# Xbee.net
KiCad netlist of a schematic drawn in Altium Designer
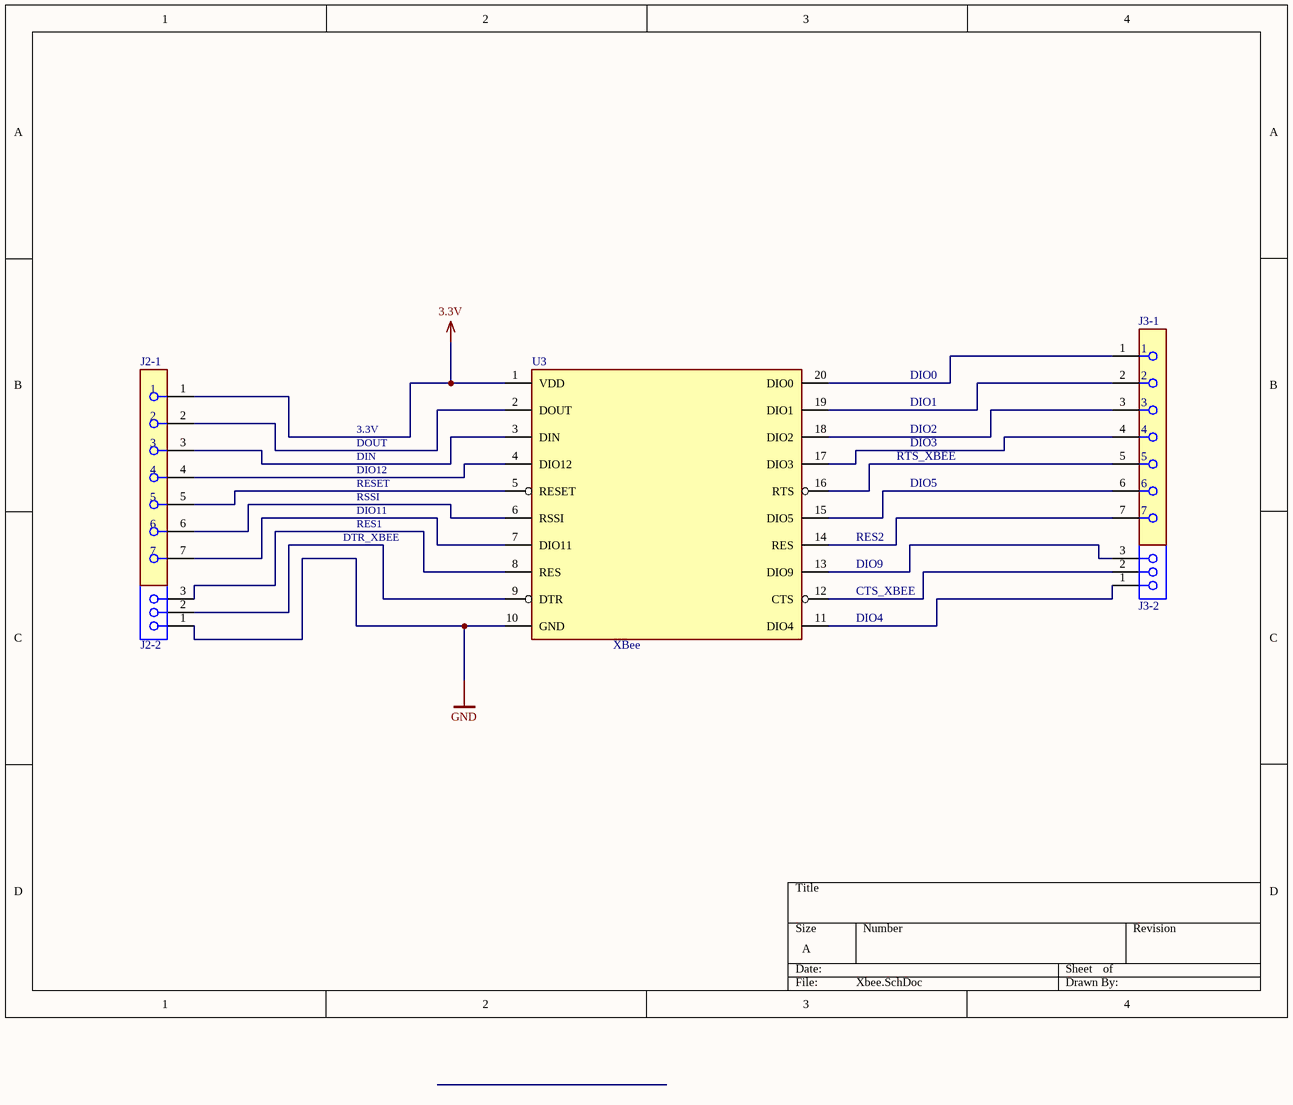
[diagram p0: Xbee.SchDoc]

(export (version "E")
  (design (tool "Eeschema 10.0.6"))
  (components
    (comp (ref "J2-1")
      (value "SSM-107-L-SV-BE")
      (footprint "FP-SSM-107-L-SV-BE-MFG")
      (description "CONN RCPT 7POS 0.1 GOLD SMD")
      (libsource (lib "") (part "e5664c6fdf629e95b354a88b8d4375b_1"))
    )
    (comp (ref "J2-2")
      (value "SSM-103-L-SV")
      (footprint "SMTC-SSM-103-X-SV")
      (description "Tiger Claw(TM) Surface Mount Socket, Vertical, -55 to 125 degC, 2.54 mm Pitch, 3-Pin, Female, RoHS")
      (fields (field (name "MANUFACTURER") "Samtec"))
      (libsource (lib "Altium Content Vault") (part "SMTC-SSM-103-X-SV"))
    )
    (comp (ref "J3-1")
      (value "SSM-107-L-SV-BE")
      (footprint "FP-SSM-107-L-SV-BE-MFG")
      (description "CONN RCPT 7POS 0.1 GOLD SMD")
      (libsource (lib "Altium Content Vault") (part "e5664c6fdf629e95b354a88b8d4375b"))
    )
    (comp (ref "J3-2")
      (value "SSM-103-L-SV")
      (footprint "SMTC-SSM-103-X-SV")
      (description "Tiger Claw(TM) Surface Mount Socket, Vertical, -55 to 125 degC, 2.54 mm Pitch, 3-Pin, Female, RoHS")
      (fields (field (name "MANUFACTURER") "Samtec"))
      (libsource (lib "Altium Content Vault") (part "SMTC-SSM-103-X-SV"))
    )
    (comp (ref "U3")
      (value "XBee")
      (footprint "FP-XBP9B-DMUTB002-MFG")
      (description "RX TXRX MOD ISM < 1GHZ U.FL TH")
      (libsource (lib "Components - 20.07.25 - 17.24") (part "CMP-84319-000004-1"))
    )
  )
  (nets
    (net (code "1") (name "3.3V") (class "Default")
      (node (ref "J2-1") (pin "1") (pinfunction "1_1") (pintype "passive"))
      (node (ref "U3") (pin "1") (pinfunction "VDD_1") (pintype "power_in"))
    )
    (net (code "2") (name "GND") (class "Default")
      (node (ref "J2-2") (pin "1") (pinfunction "1_1") (pintype "passive"))
      (node (ref "U3") (pin "10") (pinfunction "GND_10") (pintype "power_in"))
    )
    (net (code "3") (name "Net-(J2-2-Pad3)") (class "Default")
      (node (ref "J2-2") (pin "3") (pinfunction "3_3") (pintype "passive"))
      (node (ref "U3") (pin "8") (pinfunction "RES_8") (pintype "passive"))
    )
    (net (code "4") (name "Net-(J3-1-Pad7)") (class "Default")
      (node (ref "J3-1") (pin "7") (pinfunction "7_7") (pintype "passive"))
      (node (ref "U3") (pin "14") (pinfunction "RES_14") (pintype "passive"))
    )
    (net (code "5") (name "Net-(U3-CTS)") (class "Default")
      (node (ref "J3-2") (pin "2") (pinfunction "2_2") (pintype "passive"))
      (node (ref "U3") (pin "12") (pinfunction "CTS_12") (pintype "passive"))
    )
    (net (code "6") (name "Net-(U3-DIN)") (class "Default")
      (node (ref "J2-1") (pin "3") (pinfunction "3_3") (pintype "passive"))
      (node (ref "U3") (pin "3") (pinfunction "DIN_3") (pintype "passive"))
    )
    (net (code "7") (name "Net-(U3-DIO0)") (class "Default")
      (node (ref "J3-1") (pin "1") (pinfunction "1_1") (pintype "passive"))
      (node (ref "U3") (pin "20") (pinfunction "DIO0_20") (pintype "passive"))
    )
    (net (code "8") (name "Net-(U3-DIO1)") (class "Default")
      (node (ref "J3-1") (pin "2") (pinfunction "2_2") (pintype "passive"))
      (node (ref "U3") (pin "19") (pinfunction "DIO1_19") (pintype "passive"))
    )
    (net (code "9") (name "Net-(U3-DIO2)") (class "Default")
      (node (ref "J3-1") (pin "3") (pinfunction "3_3") (pintype "passive"))
      (node (ref "U3") (pin "18") (pinfunction "DIO2_18") (pintype "passive"))
    )
    (net (code "10") (name "Net-(U3-DIO3)") (class "Default")
      (node (ref "J3-1") (pin "4") (pinfunction "4_4") (pintype "passive"))
      (node (ref "U3") (pin "17") (pinfunction "DIO3_17") (pintype "passive"))
    )
    (net (code "11") (name "Net-(U3-DIO4)") (class "Default")
      (node (ref "J3-2") (pin "1") (pinfunction "1_1") (pintype "passive"))
      (node (ref "U3") (pin "11") (pinfunction "DIO4_11") (pintype "passive"))
    )
    (net (code "12") (name "Net-(U3-DIO5)") (class "Default")
      (node (ref "J3-1") (pin "6") (pinfunction "6_6") (pintype "passive"))
      (node (ref "U3") (pin "15") (pinfunction "DIO5_15") (pintype "passive"))
    )
    (net (code "13") (name "Net-(U3-DIO9)") (class "Default")
      (node (ref "J3-2") (pin "3") (pinfunction "3_3") (pintype "passive"))
      (node (ref "U3") (pin "13") (pinfunction "DIO9_13") (pintype "passive"))
    )
    (net (code "14") (name "Net-(U3-DIO11)") (class "Default")
      (node (ref "J2-1") (pin "7") (pinfunction "7_7") (pintype "passive"))
      (node (ref "U3") (pin "7") (pinfunction "DIO11_7") (pintype "passive"))
    )
    (net (code "15") (name "Net-(U3-DIO12)") (class "Default")
      (node (ref "J2-1") (pin "4") (pinfunction "4_4") (pintype "passive"))
      (node (ref "U3") (pin "4") (pinfunction "DIO12_4") (pintype "passive"))
    )
    (net (code "16") (name "Net-(U3-DOUT)") (class "Default")
      (node (ref "J2-1") (pin "2") (pinfunction "2_2") (pintype "passive"))
      (node (ref "U3") (pin "2") (pinfunction "DOUT_2") (pintype "passive"))
    )
    (net (code "17") (name "Net-(U3-DTR)") (class "Default")
      (node (ref "J2-2") (pin "2") (pinfunction "2_2") (pintype "passive"))
      (node (ref "U3") (pin "9") (pinfunction "DTR_9") (pintype "passive"))
    )
    (net (code "18") (name "Net-(U3-RESET)") (class "Default")
      (node (ref "J2-1") (pin "5") (pinfunction "5_5") (pintype "passive"))
      (node (ref "U3") (pin "5") (pinfunction "RESET_5") (pintype "passive"))
    )
    (net (code "19") (name "Net-(U3-RSSI)") (class "Default")
      (node (ref "J2-1") (pin "6") (pinfunction "6_6") (pintype "passive"))
      (node (ref "U3") (pin "6") (pinfunction "RSSI_6") (pintype "passive"))
    )
    (net (code "20") (name "Net-(U3-RTS)") (class "Default")
      (node (ref "J3-1") (pin "5") (pinfunction "5_5") (pintype "passive"))
      (node (ref "U3") (pin "16") (pinfunction "RTS_16") (pintype "passive"))
    )
  )
)
